# Schematic.net
KiCad netlist of a schematic drawn in Altium Designer
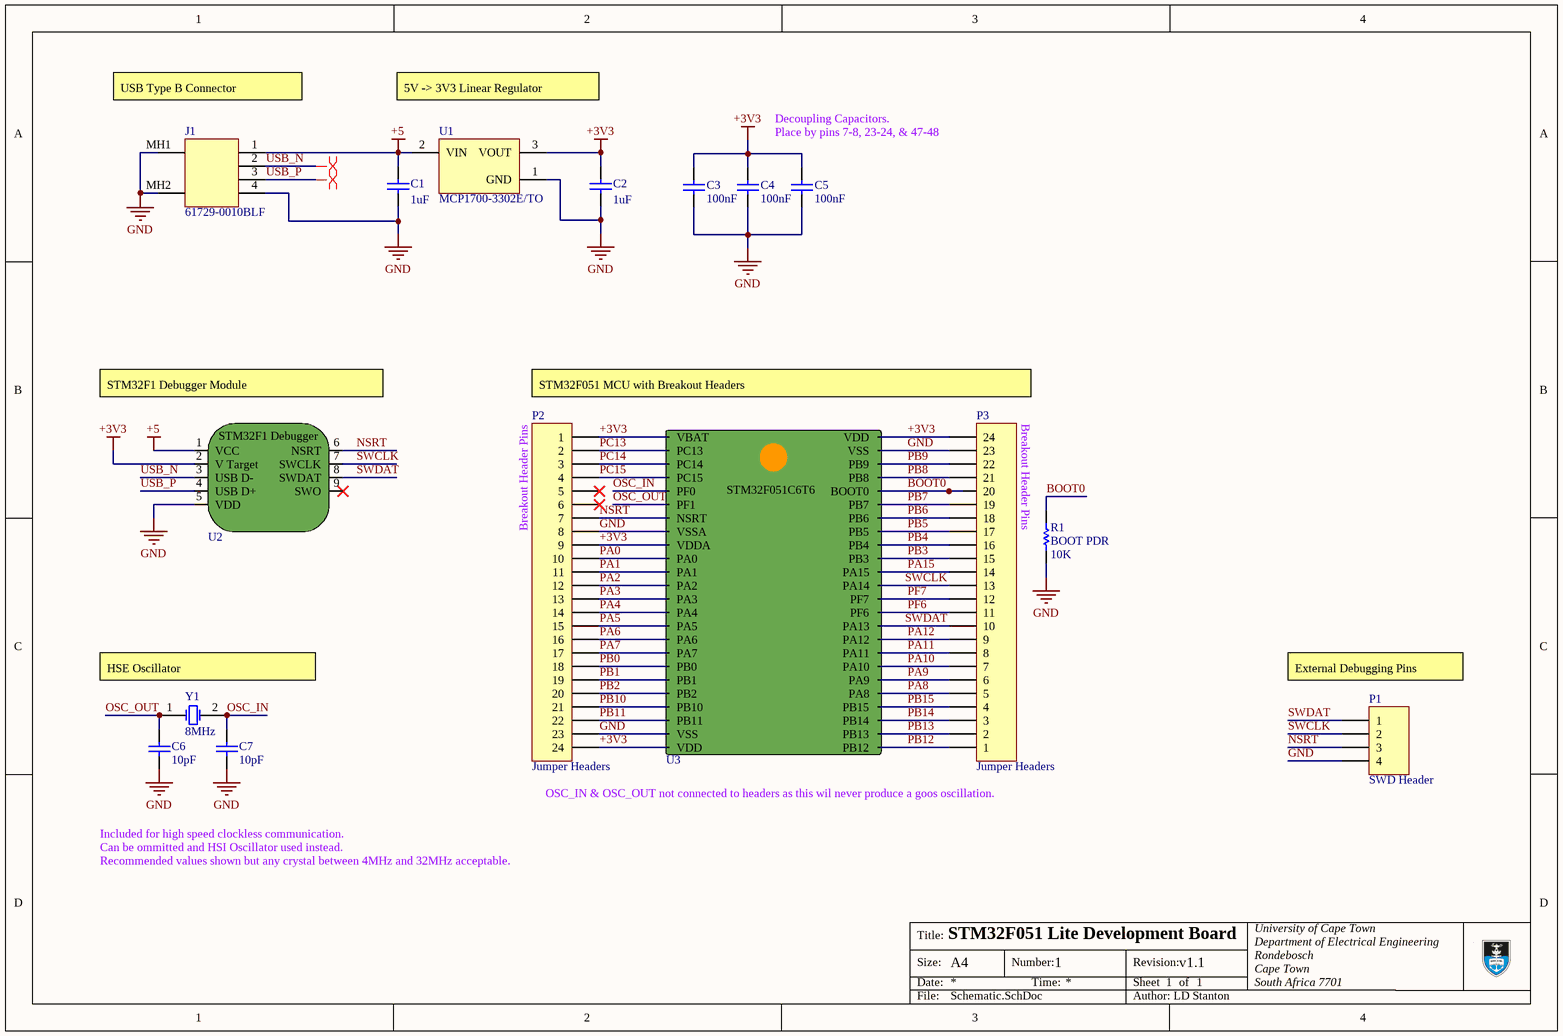
[diagram p0: Schematic.SchDoc]

(export (version "E")
  (design (tool "Eeschema 10.0.6"))
  (components
    (comp (ref "C1")
      (value "1uF")
      (footprint "200mil Capacitor THT")
      (description "Capacitor")
      (fields (field (name "Comment") "Ceramic Capacitor") (field (name "PUBLISHER") "Altium Limited"))
      (libsource (lib "Miscellaneous Devices") (part "Cap"))
    )
    (comp (ref "C2")
      (value "1uF")
      (footprint "200mil Capacitor THT")
      (description "Capacitor")
      (fields (field (name "Comment") "Ceramic Capacitor") (field (name "PUBLISHER") "Altium Limited"))
      (libsource (lib "Miscellaneous Devices") (part "Cap"))
    )
    (comp (ref "C3")
      (value "100nF")
      (footprint "100mil Capacitor THT")
      (description "Capacitor")
      (fields (field (name "Comment") "Ceramic Capacitor") (field (name "PUBLISHER") "Altium Limited"))
      (libsource (lib "Miscellaneous Devices") (part "Cap"))
    )
    (comp (ref "C4")
      (value "100nF")
      (footprint "100mil Capacitor THT")
      (description "Capacitor")
      (fields (field (name "Comment") "Ceramic Capacitor") (field (name "PUBLISHER") "Altium Limited"))
      (libsource (lib "Miscellaneous Devices") (part "Cap"))
    )
    (comp (ref "C5")
      (value "100nF")
      (footprint "100mil Capacitor THT")
      (description "Capacitor")
      (fields (field (name "Comment") "Ceramic Capacitor") (field (name "PUBLISHER") "Altium Limited"))
      (libsource (lib "Miscellaneous Devices") (part "Cap"))
    )
    (comp (ref "C6")
      (value "10pF")
      (footprint "100mil Capacitor THT")
      (description "Capacitor")
      (fields (field (name "Comment") "Ceramic Capacitor") (field (name "PUBLISHER") "Altium Limited"))
      (libsource (lib "Miscellaneous Devices") (part "Cap"))
    )
    (comp (ref "C7")
      (value "10pF")
      (footprint "100mil Capacitor THT")
      (description "Capacitor")
      (fields (field (name "Comment") "Ceramic Capacitor") (field (name "PUBLISHER") "Altium Limited"))
      (libsource (lib "Miscellaneous Devices") (part "Cap"))
    )
    (comp (ref "J1")
      (value "61729-0010BLF")
      (footprint "FCI-61729-0010BLF-6_V")
      (description "Single USB 2.0, B Type, Right Angle Jack, Through Hole, RoHS, Tube")
      (fields (field (name "MANUFACTURER") "FCI Electronics"))
      (libsource (lib "Altium Content Vault") (part "FCI-CN-1F-R6"))
    )
    (comp (ref "P1")
      (value "SWD Header")
      (footprint "HDR1X4H")
      (description "Header, 4-Pin, Right Angle")
      (fields (field (name "PUBLISHER") "Altium Limited"))
      (libsource (lib "Miscellaneous Connectors") (part "Header 4H"))
    )
    (comp (ref "P2")
      (value "Jumper Headers")
      (footprint "HDR1X24")
      (description "Header, 24-Pin")
      (fields (field (name "PUBLISHER") "Altium Limited"))
      (libsource (lib "Miscellaneous Connectors") (part "Header 24"))
    )
    (comp (ref "P3")
      (value "Jumper Headers")
      (footprint "HDR1X24")
      (description "Header, 24-Pin")
      (fields (field (name "PUBLISHER") "Altium Limited"))
      (libsource (lib "") (part "Header 24_1"))
    )
    (comp (ref "R1")
      (value "BOOT PDR")
      (footprint "AXIAL-0.3")
      (description "Resistor")
      (fields (field (name "ALTIUM_VALUE") "10K") (field (name "PUBLISHER") "Altium Limited"))
      (libsource (lib "Miscellaneous Devices") (part "Res1"))
    )
    (comp (ref "U1")
      (value "MCP1700-3302E/TO")
      (footprint "TO-92-TO3")
      (description "Low Quiescent Current LDO, 3-Pin TO-92, Extended TemperatureBAG")
      (fields (field (name "PUBLISHER") "Altium Limited"))
      (libsource (lib "Microchip Power Mgt Line Regulator") (part "MCP1700-3302E/TO"))
    )
    (comp (ref "U2")
      (value "STM32F1 Debugger")
      (footprint "STM Debugger")
      (libsource (lib "STM32F051C6 Lite Development Board") (part "STM32F1 Debugger"))
    )
    (comp (ref "U3")
      (value "STM32F051C6T6 Baracuda Breakout")
      (footprint "STM32F051C6T6 Baracuda Breakout")
      (libsource (lib "STM32F051C6 Lite Development Board") (part "STM32F051C6T6 Baracuda Breakout"))
    )
    (comp (ref "Y1")
      (value "8MHz")
      (footprint "200mil Flat Quarts Crystal THT")
      (description "Crystal Oscillator")
      (fields (field (name "PUBLISHER") "Altium Limited"))
      (libsource (lib "Miscellaneous Devices") (part "XTAL"))
    )
  )
  (nets
    (net (code "1") (name "+3V3") (class "Default")
      (node (ref "C2") (pin "1") (pinfunction "1_1") (pintype "passive"))
      (node (ref "C3") (pin "1") (pinfunction "1_1") (pintype "passive"))
      (node (ref "C4") (pin "1") (pinfunction "1_1") (pintype "passive"))
      (node (ref "C5") (pin "1") (pinfunction "1_1") (pintype "passive"))
      (node (ref "P2") (pin "1") (pinfunction "1_1") (pintype "passive"))
      (node (ref "P2") (pin "24") (pinfunction "24_24") (pintype "passive"))
      (node (ref "P2") (pin "9") (pinfunction "9_9") (pintype "passive"))
      (node (ref "P3") (pin "24") (pinfunction "24_24") (pintype "passive"))
      (node (ref "U1") (pin "3") (pinfunction "VOUT_3") (pintype "power_in"))
      (node (ref "U2") (pin "2") (pinfunction "V_Target_2") (pintype "passive"))
      (node (ref "U3") (pin "1") (pinfunction "VBAT_1") (pintype "input"))
      (node (ref "U3") (pin "24") (pinfunction "VDD_24") (pintype "power_in"))
      (node (ref "U3") (pin "48") (pinfunction "VDD_48") (pintype "power_in"))
      (node (ref "U3") (pin "9") (pinfunction "VDDA_9") (pintype "power_in"))
    )
    (net (code "2") (name "+5") (class "Default")
      (node (ref "C1") (pin "1") (pinfunction "1_1") (pintype "passive"))
      (node (ref "J1") (pin "1") (pinfunction "1_1") (pintype "passive"))
      (node (ref "U1") (pin "2") (pinfunction "VIN_2") (pintype "power_in"))
      (node (ref "U2") (pin "1") (pinfunction "VCC_1") (pintype "passive"))
    )
    (net (code "3") (name "/BOOT0") (class "Default")
      (node (ref "P3") (pin "20") (pinfunction "20_20") (pintype "passive"))
      (node (ref "R1") (pin "1") (pinfunction "1_1") (pintype "passive"))
      (node (ref "U3") (pin "44") (pinfunction "BOOT0_44") (pintype "input"))
    )
    (net (code "4") (name "/NSRT") (class "Default")
      (node (ref "P1") (pin "3") (pinfunction "3_3") (pintype "passive"))
      (node (ref "P2") (pin "7") (pinfunction "7_7") (pintype "passive"))
      (node (ref "U2") (pin "6") (pinfunction "NSRT_6") (pintype "passive"))
      (node (ref "U3") (pin "7") (pinfunction "NSRT_7") (pintype "input"))
    )
    (net (code "5") (name "/OSC_IN") (class "Default")
      (node (ref "C7") (pin "1") (pinfunction "1_1") (pintype "passive"))
      (node (ref "U3") (pin "5") (pinfunction "PF0_5") (pintype "input"))
      (node (ref "Y1") (pin "2") (pinfunction "OSC2_2") (pintype "passive"))
    )
    (net (code "6") (name "/OSC_OUT") (class "Default")
      (node (ref "C6") (pin "1") (pinfunction "1_1") (pintype "passive"))
      (node (ref "U3") (pin "6") (pinfunction "PF1_6") (pintype "input"))
      (node (ref "Y1") (pin "1") (pinfunction "OSC1_1") (pintype "passive"))
    )
    (net (code "7") (name "/PA0") (class "Default")
      (node (ref "P2") (pin "10") (pinfunction "10_10") (pintype "passive"))
      (node (ref "U3") (pin "10") (pinfunction "PA0_10") (pintype "bidirectional"))
    )
    (net (code "8") (name "/PA1") (class "Default")
      (node (ref "P2") (pin "11") (pinfunction "11_11") (pintype "passive"))
      (node (ref "U3") (pin "11") (pinfunction "PA1_11") (pintype "bidirectional"))
    )
    (net (code "9") (name "/PA2") (class "Default")
      (node (ref "P2") (pin "12") (pinfunction "12_12") (pintype "passive"))
      (node (ref "U3") (pin "12") (pinfunction "PA2_12") (pintype "bidirectional"))
    )
    (net (code "10") (name "/PA3") (class "Default")
      (node (ref "P2") (pin "13") (pinfunction "13_13") (pintype "passive"))
      (node (ref "U3") (pin "13") (pinfunction "PA3_13") (pintype "bidirectional"))
    )
    (net (code "11") (name "/PA4") (class "Default")
      (node (ref "P2") (pin "14") (pinfunction "14_14") (pintype "passive"))
      (node (ref "U3") (pin "14") (pinfunction "PA4_14") (pintype "bidirectional"))
    )
    (net (code "12") (name "/PA5") (class "Default")
      (node (ref "P2") (pin "15") (pinfunction "15_15") (pintype "passive"))
      (node (ref "U3") (pin "15") (pinfunction "PA5_15") (pintype "bidirectional"))
    )
    (net (code "13") (name "/PA6") (class "Default")
      (node (ref "P2") (pin "16") (pinfunction "16_16") (pintype "passive"))
      (node (ref "U3") (pin "16") (pinfunction "PA6_16") (pintype "bidirectional"))
    )
    (net (code "14") (name "/PA7") (class "Default")
      (node (ref "P2") (pin "17") (pinfunction "17_17") (pintype "passive"))
      (node (ref "U3") (pin "17") (pinfunction "PA7_17") (pintype "bidirectional"))
    )
    (net (code "15") (name "/PA8") (class "Default")
      (node (ref "P3") (pin "5") (pinfunction "5_5") (pintype "passive"))
      (node (ref "U3") (pin "29") (pinfunction "PA8_29") (pintype "bidirectional"))
    )
    (net (code "16") (name "/PA9") (class "Default")
      (node (ref "P3") (pin "6") (pinfunction "6_6") (pintype "passive"))
      (node (ref "U3") (pin "30") (pinfunction "PA9_30") (pintype "bidirectional"))
    )
    (net (code "17") (name "/PA10") (class "Default")
      (node (ref "P3") (pin "7") (pinfunction "7_7") (pintype "passive"))
      (node (ref "U3") (pin "31") (pinfunction "PA10_31") (pintype "bidirectional"))
    )
    (net (code "18") (name "/PA11") (class "Default")
      (node (ref "P3") (pin "8") (pinfunction "8_8") (pintype "passive"))
      (node (ref "U3") (pin "32") (pinfunction "PA11_32") (pintype "bidirectional"))
    )
    (net (code "19") (name "/PA12") (class "Default")
      (node (ref "P3") (pin "9") (pinfunction "9_9") (pintype "passive"))
      (node (ref "U3") (pin "33") (pinfunction "PA12_33") (pintype "bidirectional"))
    )
    (net (code "20") (name "/PA15") (class "Default")
      (node (ref "P3") (pin "14") (pinfunction "14_14") (pintype "passive"))
      (node (ref "U3") (pin "38") (pinfunction "PA15_38") (pintype "bidirectional"))
    )
    (net (code "21") (name "/PB0") (class "Default")
      (node (ref "P2") (pin "18") (pinfunction "18_18") (pintype "passive"))
      (node (ref "U3") (pin "18") (pinfunction "PB0_18") (pintype "bidirectional"))
    )
    (net (code "22") (name "/PB1") (class "Default")
      (node (ref "P2") (pin "19") (pinfunction "19_19") (pintype "passive"))
      (node (ref "U3") (pin "19") (pinfunction "PB1_19") (pintype "bidirectional"))
    )
    (net (code "23") (name "/PB2") (class "Default")
      (node (ref "P2") (pin "20") (pinfunction "20_20") (pintype "passive"))
      (node (ref "U3") (pin "20") (pinfunction "PB2_20") (pintype "bidirectional"))
    )
    (net (code "24") (name "/PB3") (class "Default")
      (node (ref "P3") (pin "15") (pinfunction "15_15") (pintype "passive"))
      (node (ref "U3") (pin "39") (pinfunction "PB3_39") (pintype "bidirectional"))
    )
    (net (code "25") (name "/PB4") (class "Default")
      (node (ref "P3") (pin "16") (pinfunction "16_16") (pintype "passive"))
      (node (ref "U3") (pin "40") (pinfunction "PB4_40") (pintype "bidirectional"))
    )
    (net (code "26") (name "/PB5") (class "Default")
      (node (ref "P3") (pin "17") (pinfunction "17_17") (pintype "passive"))
      (node (ref "U3") (pin "41") (pinfunction "PB5_41") (pintype "bidirectional"))
    )
    (net (code "27") (name "/PB6") (class "Default")
      (node (ref "P3") (pin "18") (pinfunction "18_18") (pintype "passive"))
      (node (ref "U3") (pin "42") (pinfunction "PB6_42") (pintype "bidirectional"))
    )
    (net (code "28") (name "/PB7") (class "Default")
      (node (ref "P3") (pin "19") (pinfunction "19_19") (pintype "passive"))
      (node (ref "U3") (pin "43") (pinfunction "PB7_43") (pintype "bidirectional"))
    )
    (net (code "29") (name "/PB8") (class "Default")
      (node (ref "P3") (pin "21") (pinfunction "21_21") (pintype "passive"))
      (node (ref "U3") (pin "45") (pinfunction "PB8_45") (pintype "bidirectional"))
    )
    (net (code "30") (name "/PB9") (class "Default")
      (node (ref "P3") (pin "22") (pinfunction "22_22") (pintype "passive"))
      (node (ref "U3") (pin "46") (pinfunction "PB9_46") (pintype "bidirectional"))
    )
    (net (code "31") (name "/PB10") (class "Default")
      (node (ref "P2") (pin "21") (pinfunction "21_21") (pintype "passive"))
      (node (ref "U3") (pin "21") (pinfunction "PB10_21") (pintype "bidirectional"))
    )
    (net (code "32") (name "/PB11") (class "Default")
      (node (ref "P2") (pin "22") (pinfunction "22_22") (pintype "passive"))
      (node (ref "U3") (pin "22") (pinfunction "PB11_22") (pintype "bidirectional"))
    )
    (net (code "33") (name "/PB12") (class "Default")
      (node (ref "P3") (pin "1") (pinfunction "1_1") (pintype "passive"))
      (node (ref "U3") (pin "25") (pinfunction "PB12_25") (pintype "bidirectional"))
    )
    (net (code "34") (name "/PB13") (class "Default")
      (node (ref "P3") (pin "2") (pinfunction "2_2") (pintype "passive"))
      (node (ref "U3") (pin "26") (pinfunction "PB13_26") (pintype "bidirectional"))
    )
    (net (code "35") (name "/PB14") (class "Default")
      (node (ref "P3") (pin "3") (pinfunction "3_3") (pintype "passive"))
      (node (ref "U3") (pin "27") (pinfunction "PB14_27") (pintype "bidirectional"))
    )
    (net (code "36") (name "/PB15") (class "Default")
      (node (ref "P3") (pin "4") (pinfunction "4_4") (pintype "passive"))
      (node (ref "U3") (pin "28") (pinfunction "PB15_28") (pintype "bidirectional"))
    )
    (net (code "37") (name "/PC13") (class "Default")
      (node (ref "P2") (pin "2") (pinfunction "2_2") (pintype "passive"))
      (node (ref "U3") (pin "2") (pinfunction "PC13_2") (pintype "bidirectional"))
    )
    (net (code "38") (name "/PC14") (class "Default")
      (node (ref "P2") (pin "3") (pinfunction "3_3") (pintype "passive"))
      (node (ref "U3") (pin "3") (pinfunction "PC14_3") (pintype "bidirectional"))
    )
    (net (code "39") (name "/PC15") (class "Default")
      (node (ref "P2") (pin "4") (pinfunction "4_4") (pintype "passive"))
      (node (ref "U3") (pin "4") (pinfunction "PC15_4") (pintype "bidirectional"))
    )
    (net (code "40") (name "/PF6") (class "Default")
      (node (ref "P3") (pin "11") (pinfunction "11_11") (pintype "passive"))
      (node (ref "U3") (pin "35") (pinfunction "PF6_35") (pintype "bidirectional"))
    )
    (net (code "41") (name "/PF7") (class "Default")
      (node (ref "P3") (pin "12") (pinfunction "12_12") (pintype "passive"))
      (node (ref "U3") (pin "36") (pinfunction "PF7_36") (pintype "bidirectional"))
    )
    (net (code "42") (name "/SWCLK") (class "Default")
      (node (ref "P1") (pin "2") (pinfunction "2_2") (pintype "passive"))
      (node (ref "P3") (pin "13") (pinfunction "13_13") (pintype "passive"))
      (node (ref "U2") (pin "7") (pinfunction "SWCLK_7") (pintype "passive"))
      (node (ref "U3") (pin "37") (pinfunction "PA14_37") (pintype "bidirectional"))
    )
    (net (code "43") (name "/SWDAT") (class "Default")
      (node (ref "P1") (pin "1") (pinfunction "1_1") (pintype "passive"))
      (node (ref "P3") (pin "10") (pinfunction "10_10") (pintype "passive"))
      (node (ref "U2") (pin "8") (pinfunction "SWDAT_8") (pintype "passive"))
      (node (ref "U3") (pin "34") (pinfunction "PA13_34") (pintype "bidirectional"))
    )
    (net (code "44") (name "/USB_N") (class "Default")
      (node (ref "J1") (pin "2") (pinfunction "2_2") (pintype "passive"))
      (node (ref "U2") (pin "3") (pinfunction "USB_D-_3") (pintype "passive"))
    )
    (net (code "45") (name "/USB_P") (class "Default")
      (node (ref "J1") (pin "3") (pinfunction "3_3") (pintype "passive"))
      (node (ref "U2") (pin "4") (pinfunction "USB_D+_4") (pintype "passive"))
    )
    (net (code "46") (name "GND") (class "Default")
      (node (ref "C1") (pin "2") (pinfunction "2_2") (pintype "passive"))
      (node (ref "C2") (pin "2") (pinfunction "2_2") (pintype "passive"))
      (node (ref "C3") (pin "2") (pinfunction "2_2") (pintype "passive"))
      (node (ref "C4") (pin "2") (pinfunction "2_2") (pintype "passive"))
      (node (ref "C5") (pin "2") (pinfunction "2_2") (pintype "passive"))
      (node (ref "C6") (pin "2") (pinfunction "2_2") (pintype "passive"))
      (node (ref "C7") (pin "2") (pinfunction "2_2") (pintype "passive"))
      (node (ref "J1") (pin "4") (pinfunction "4_4") (pintype "passive"))
      (node (ref "J1") (pin "MH1") (pinfunction "MH1_MH1") (pintype "passive"))
      (node (ref "J1") (pin "MH2") (pinfunction "MH2_MH2") (pintype "passive"))
      (node (ref "P1") (pin "4") (pinfunction "4_4") (pintype "passive"))
      (node (ref "P2") (pin "23") (pinfunction "23_23") (pintype "passive"))
      (node (ref "P2") (pin "8") (pinfunction "8_8") (pintype "passive"))
      (node (ref "P3") (pin "23") (pinfunction "23_23") (pintype "passive"))
      (node (ref "R1") (pin "2") (pinfunction "2_2") (pintype "passive"))
      (node (ref "U1") (pin "1") (pinfunction "GND_1") (pintype "power_in"))
      (node (ref "U2") (pin "5") (pinfunction "VDD_5") (pintype "passive"))
      (node (ref "U3") (pin "23") (pinfunction "VSS_23") (pintype "power_in"))
      (node (ref "U3") (pin "47") (pinfunction "VSS_47") (pintype "power_in"))
      (node (ref "U3") (pin "8") (pinfunction "VSSA_8") (pintype "power_in"))
    )
    (net (code "47") (name "unconnected-(P2-Pad5)") (class "Default")
      (node (ref "P2") (pin "5") (pinfunction "5_5") (pintype "passive+no_connect"))
    )
    (net (code "48") (name "unconnected-(P2-Pad6)") (class "Default")
      (node (ref "P2") (pin "6") (pinfunction "6_6") (pintype "passive+no_connect"))
    )
    (net (code "49") (name "unconnected-(U2-SWO-Pad9)") (class "Default")
      (node (ref "U2") (pin "9") (pinfunction "SWO_9") (pintype "passive+no_connect"))
    )
  )
)
